# Arduino-4_Relays-Shield-V1.net
KiCad netlist of a schematic drawn in EAGLE
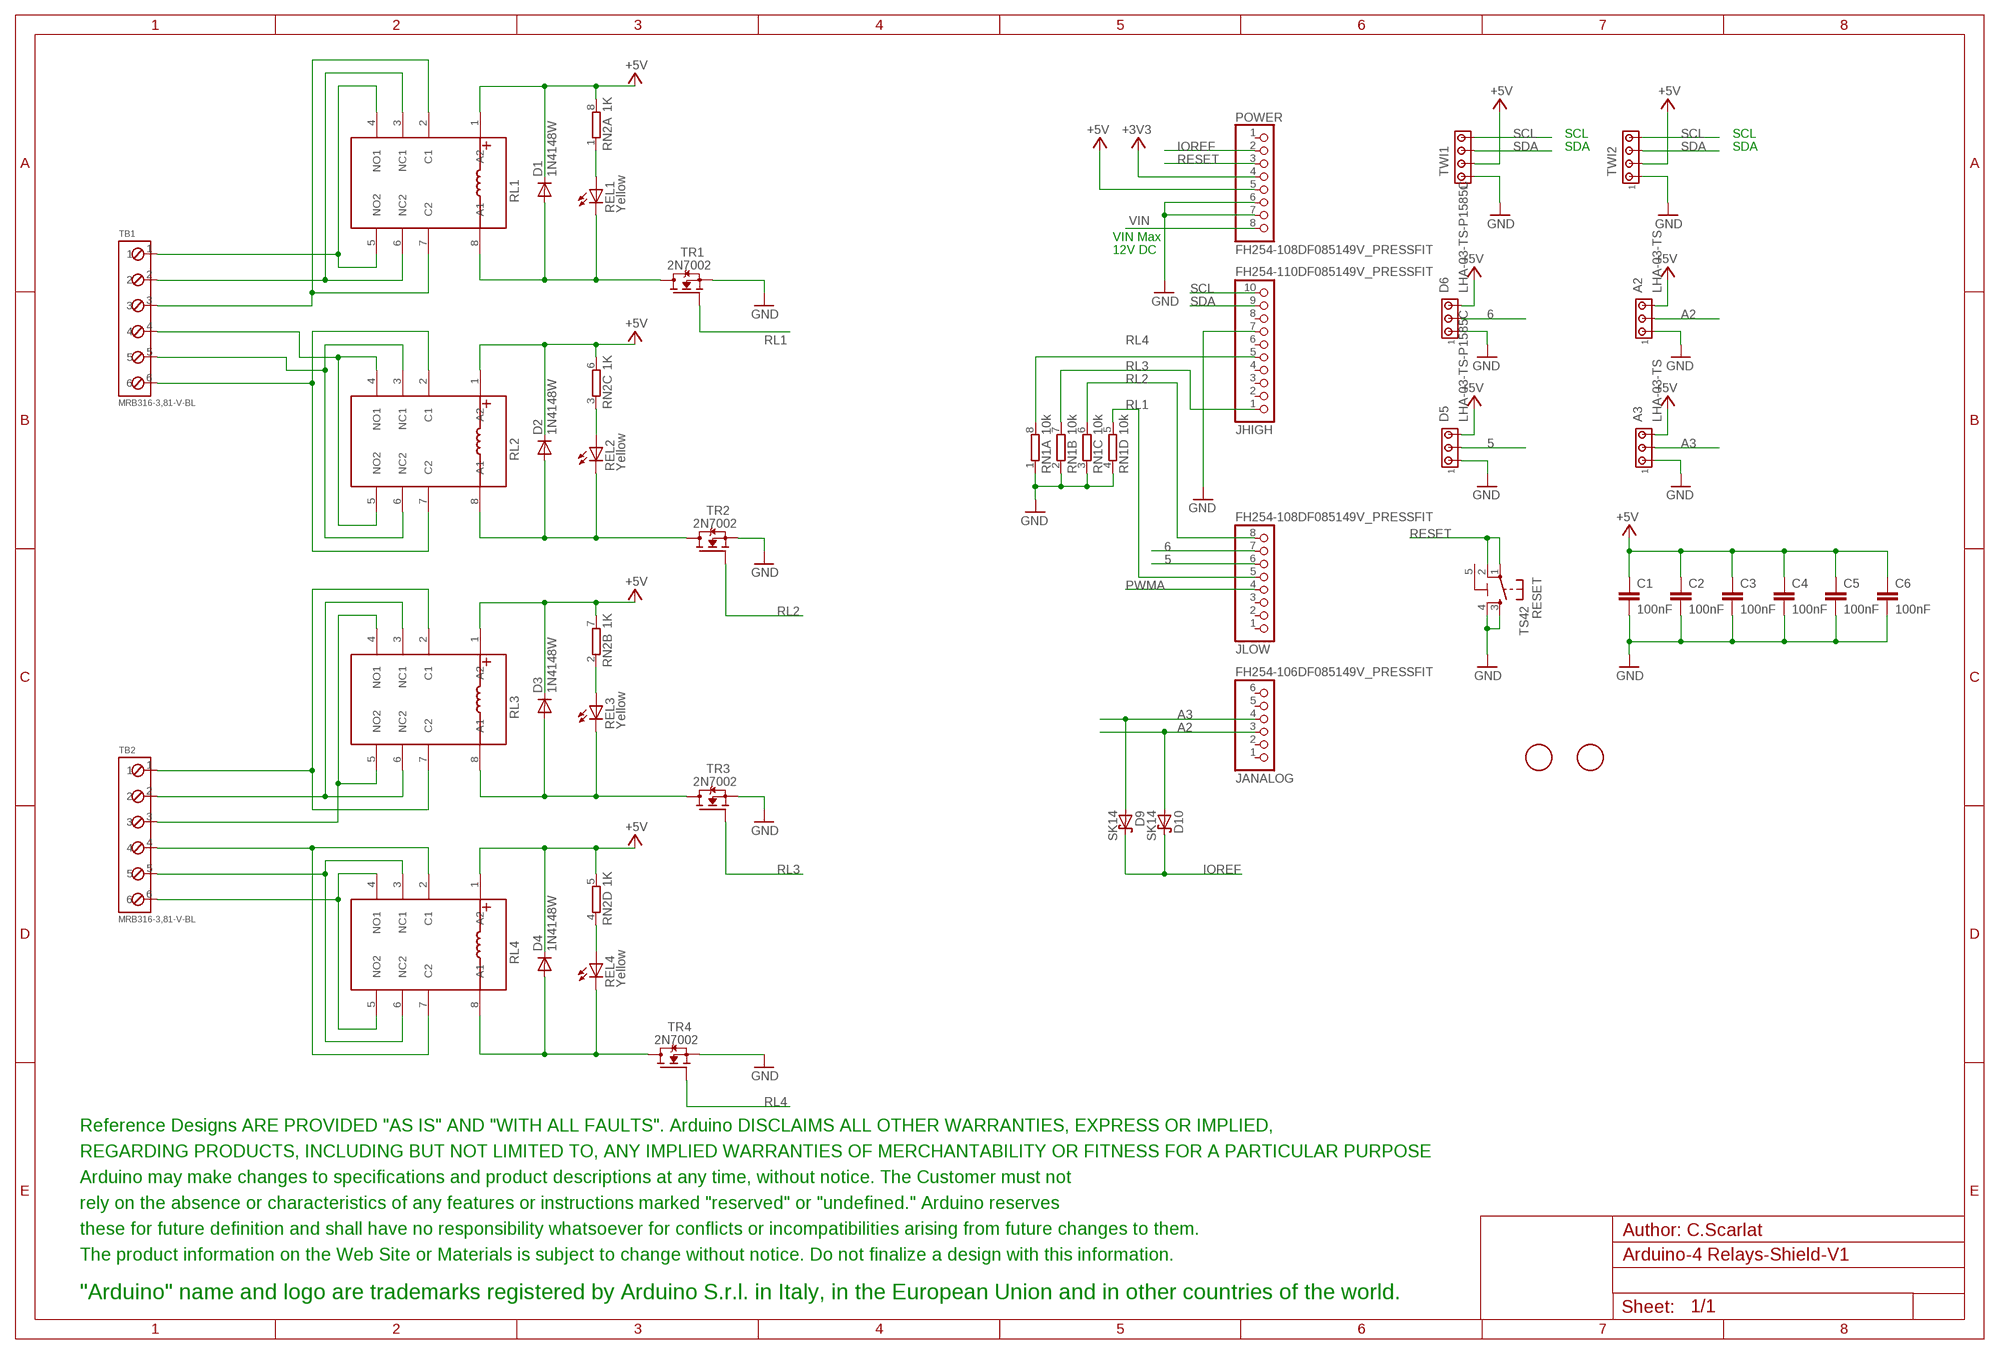
[diagram p0: schematic, sheet 1]

(export (version "E")
  (design (tool "Eeschema 10.0.6"))
  (components
    (comp (ref "A2")
      (value "LHA-03-TS")
      (footprint "eagle-import:10X03MTA")
      (libsource (lib "eagle-import") (part "0141_LHA-03-TS"))
    )
    (comp (ref "A3")
      (value "LHA-03-TS")
      (footprint "eagle-import:10X03MTA")
      (libsource (lib "eagle-import") (part "0141_LHA-03-TS"))
    )
    (comp (ref "C1")
      (value "100nF")
      (footprint "eagle-import:C0603-ROUND")
      (fields (field (name "PART_NUMBER") "cl10b104kbnc"))
      (libsource (lib "eagle-import") (part "0015_100NF_0603"))
    )
    (comp (ref "C2")
      (value "100nF")
      (footprint "eagle-import:C0603-ROUND")
      (fields (field (name "PART_NUMBER") "cl10b104kbnc"))
      (libsource (lib "eagle-import") (part "0015_100NF_0603"))
    )
    (comp (ref "C3")
      (value "100nF")
      (footprint "eagle-import:C0603-ROUND")
      (fields (field (name "PART_NUMBER") "cl10b104kbnc"))
      (libsource (lib "eagle-import") (part "0015_100NF_0603"))
    )
    (comp (ref "C4")
      (value "100nF")
      (footprint "eagle-import:C0603-ROUND")
      (fields (field (name "PART_NUMBER") "cl10b104kbnc"))
      (libsource (lib "eagle-import") (part "0015_100NF_0603"))
    )
    (comp (ref "C5")
      (value "100nF")
      (footprint "eagle-import:C0603-ROUND")
      (fields (field (name "PART_NUMBER") "cl10b104kbnc"))
      (libsource (lib "eagle-import") (part "0015_100NF_0603"))
    )
    (comp (ref "C6")
      (value "100nF")
      (footprint "eagle-import:C0603-ROUND")
      (fields (field (name "PART_NUMBER") "cl10b104kbnc"))
      (libsource (lib "eagle-import") (part "0015_100NF_0603"))
    )
    (comp (ref "D1")
      (value "1N4148W")
      (footprint "eagle-import:SOD123")
      (libsource (lib "eagle-import") (part "0290_1N4148W"))
    )
    (comp (ref "D2")
      (value "1N4148W")
      (footprint "eagle-import:SOD123")
      (libsource (lib "eagle-import") (part "0290_1N4148W"))
    )
    (comp (ref "D3")
      (value "1N4148W")
      (footprint "eagle-import:SOD123")
      (libsource (lib "eagle-import") (part "0290_1N4148W"))
    )
    (comp (ref "D4")
      (value "1N4148W")
      (footprint "eagle-import:SOD123")
      (libsource (lib "eagle-import") (part "0290_1N4148W"))
    )
    (comp (ref "D5")
      (value "LHA-03-TS-P1585C")
      (footprint "eagle-import:10X03MTA")
      (libsource (lib "eagle-import") (part "0481_LHA-03-TS-P1585C"))
    )
    (comp (ref "D6")
      (value "LHA-03-TS-P1585C")
      (footprint "eagle-import:10X03MTA")
      (libsource (lib "eagle-import") (part "0481_LHA-03-TS-P1585C"))
    )
    (comp (ref "D9")
      (value "SK14")
      (footprint "eagle-import:SMB")
      (libsource (lib "eagle-import") (part "0234_SK14"))
    )
    (comp (ref "D10")
      (value "SK14")
      (footprint "eagle-import:SMB")
      (libsource (lib "eagle-import") (part "0234_SK14"))
    )
    (comp (ref "FID2")
      (value "FIDUCIALMOUNT")
      (footprint "eagle-import:FIDUCIA-MOUNT")
      (libsource (lib "eagle-import") (part "FIDUCIALMOUNT"))
    )
    (comp (ref "FID3")
      (value "FIDUCIALMOUNT")
      (footprint "eagle-import:FIDUCIA-MOUNT")
      (libsource (lib "eagle-import") (part "FIDUCIALMOUNT"))
    )
    (comp (ref "JANALOG")
      (value "FH254-106DF085149V_PRESSFIT")
      (footprint "eagle-import:1X06-TH-PRESSFIT")
      (fields (field (name "PART_NUMBER") "FH254-106DF085149V"))
      (libsource (lib "eagle-import") (part "0061_FH254-106DF085149VPRESSFIT"))
    )
    (comp (ref "JHIGH")
      (value "FH254-110DF085149V_PRESSFIT")
      (footprint "eagle-import:1X10-TH-PRESSFIT")
      (fields (field (name "PART_NUMBER") "FH254-110DF085149V"))
      (libsource (lib "eagle-import") (part "0063_FH254-110DF085149VPRESSFIT"))
    )
    (comp (ref "JLOW")
      (value "FH254-108DF085149V_PRESSFIT")
      (footprint "eagle-import:1X08-TH-PRESSFIT")
      (fields (field (name "PART_NUMBER") "FH254-108DF085149V"))
      (libsource (lib "eagle-import") (part "0062_FH254-108DF085149VPRESSFIT"))
    )
    (comp (ref "POWER")
      (value "FH254-108DF085149V_PRESSFIT")
      (footprint "eagle-import:1X08-TH-PRESSFIT")
      (fields (field (name "PART_NUMBER") "FH254-108DF085149V"))
      (libsource (lib "eagle-import") (part "0062_FH254-108DF085149VPRESSFIT"))
    )
    (comp (ref "REL1")
      (value "Yellow")
      (footprint "eagle-import:CHIPLED_0805")
      (fields (field (name "PART_NUMBER") "KPT-2012YC"))
      (libsource (lib "eagle-import") (part "0044_KPT-2012YC"))
    )
    (comp (ref "REL2")
      (value "Yellow")
      (footprint "eagle-import:CHIPLED_0805")
      (fields (field (name "PART_NUMBER") "KPT-2012YC"))
      (libsource (lib "eagle-import") (part "0044_KPT-2012YC"))
    )
    (comp (ref "REL3")
      (value "Yellow")
      (footprint "eagle-import:CHIPLED_0805")
      (fields (field (name "PART_NUMBER") "KPT-2012YC"))
      (libsource (lib "eagle-import") (part "0044_KPT-2012YC"))
    )
    (comp (ref "REL4")
      (value "Yellow")
      (footprint "eagle-import:CHIPLED_0805")
      (fields (field (name "PART_NUMBER") "KPT-2012YC"))
      (libsource (lib "eagle-import") (part "0044_KPT-2012YC"))
    )
    (comp (ref "RESET")
      (value "TS42")
      (footprint "eagle-import:TS42")
      (fields (field (name "PART_NUMBER") "IT-1157AHNP-160G-G_GTR"))
      (libsource (lib "eagle-import") (part "0946_TS42031-160W-TR-7260"))
    )
    (comp (ref "RL1")
      (value "1045_G5V-2-H1")
      (footprint "eagle-import:RELE'-30SSERIES-DIL-2X")
      (fields (field (name "PART_NUMBER") "G5V-2-H1"))
      (libsource (lib "eagle-import") (part "1045_G5V-2-H1"))
    )
    (comp (ref "RL2")
      (value "1045_G5V-2-H1")
      (footprint "eagle-import:RELE'-30SSERIES-DIL-2X")
      (fields (field (name "PART_NUMBER") "G5V-2-H1"))
      (libsource (lib "eagle-import") (part "1045_G5V-2-H1"))
    )
    (comp (ref "RL3")
      (value "1045_G5V-2-H1")
      (footprint "eagle-import:RELE'-30SSERIES-DIL-2X")
      (fields (field (name "PART_NUMBER") "G5V-2-H1"))
      (libsource (lib "eagle-import") (part "1045_G5V-2-H1"))
    )
    (comp (ref "RL4")
      (value "1045_G5V-2-H1")
      (footprint "eagle-import:RELE'-30SSERIES-DIL-2X")
      (fields (field (name "PART_NUMBER") "G5V-2-H1"))
      (libsource (lib "eagle-import") (part "1045_G5V-2-H1"))
    )
    (comp (ref "RN1")
      (value "10k")
      (footprint "eagle-import:CAY16")
      (fields (field (name "PART_NUMBER") "064R_10K_/_CAY16-103J4LF"))
      (libsource (lib "eagle-import") (part "0016_064R_10K_/_CAY16-103J4LF"))
    )
    (comp (ref "RN2")
      (value "1K")
      (footprint "eagle-import:CAY16")
      (fields (field (name "PART_NUMBER") "064R_1K_/_CAY16-102J4LF"))
      (libsource (lib "eagle-import") (part "0005_064R_1K_/_CAY16-102J4LF"))
    )
    (comp (ref "TB1")
      (value "MRB316-3,81-V-BL")
      (footprint "eagle-import:MRB316-3,81-V-BL")
      (libsource (lib "eagle-import") (part "0698_MRB316-3,81-V-BL"))
    )
    (comp (ref "TB2")
      (value "MRB316-3,81-V-BL")
      (footprint "eagle-import:MRB316-3,81-V-BL")
      (libsource (lib "eagle-import") (part "0698_MRB316-3,81-V-BL"))
    )
    (comp (ref "TR1")
      (value "2N7002")
      (footprint "eagle-import:SOT-23")
      (libsource (lib "eagle-import") (part "1612_2N7002LT1G"))
    )
    (comp (ref "TR2")
      (value "2N7002")
      (footprint "eagle-import:SOT-23")
      (libsource (lib "eagle-import") (part "1612_2N7002LT1G"))
    )
    (comp (ref "TR3")
      (value "2N7002")
      (footprint "eagle-import:SOT-23")
      (libsource (lib "eagle-import") (part "1612_2N7002LT1G"))
    )
    (comp (ref "TR4")
      (value "2N7002")
      (footprint "eagle-import:SOT-23")
      (libsource (lib "eagle-import") (part "1612_2N7002LT1G"))
    )
    (comp (ref "TWI1")
      (value "0205_LHA-04-TS__4X1_VERTICALE_BIANCO_P_2,54")
      (footprint "eagle-import:10X04MTA")
      (fields (field (name "PART_NUMBER") "LHA-04-TS__4x1_Verticale_Bianco_p_2,54"))
      (libsource (lib "eagle-import") (part "0205_LHA-04-TS__4X1_VERTICALE_BIANCO_P_2,54"))
    )
    (comp (ref "TWI2")
      (value "0205_LHA-04-TS__4X1_VERTICALE_BIANCO_P_2,54")
      (footprint "eagle-import:10X04MTA")
      (fields (field (name "PART_NUMBER") "LHA-04-TS__4x1_Verticale_Bianco_p_2,54"))
      (libsource (lib "eagle-import") (part "0205_LHA-04-TS__4X1_VERTICALE_BIANCO_P_2,54"))
    )
    (comp (ref "U$2")
      (value "DISCLAIMER-SMALL")
      (footprint "eagle-import:DISCLAIMER")
      (libsource (lib "eagle-import") (part "DISCLAIMER-SMALL"))
    )
  )
  (nets
    (net (code "1") (name "+3V3") (class "Default")
      (node (ref "POWER") (pin "4") (pinfunction "4_4") (pintype "passive"))
    )
    (net (code "2") (name "+5V") (class "Default")
      (node (ref "A2") (pin "3") (pinfunction "3_3") (pintype "passive"))
      (node (ref "A3") (pin "3") (pinfunction "3_3") (pintype "passive"))
      (node (ref "C1") (pin "1") (pinfunction "1_1") (pintype "passive"))
      (node (ref "C2") (pin "1") (pinfunction "1_1") (pintype "passive"))
      (node (ref "C3") (pin "1") (pinfunction "1_1") (pintype "passive"))
      (node (ref "C4") (pin "1") (pinfunction "1_1") (pintype "passive"))
      (node (ref "C5") (pin "1") (pinfunction "1_1") (pintype "passive"))
      (node (ref "C6") (pin "1") (pinfunction "1_1") (pintype "passive"))
      (node (ref "D1") (pin "C") (pinfunction "C_C") (pintype "passive"))
      (node (ref "D2") (pin "C") (pinfunction "C_C") (pintype "passive"))
      (node (ref "D3") (pin "C") (pinfunction "C_C") (pintype "passive"))
      (node (ref "D4") (pin "C") (pinfunction "C_C") (pintype "passive"))
      (node (ref "D5") (pin "3") (pinfunction "3_3") (pintype "passive"))
      (node (ref "D6") (pin "3") (pinfunction "3_3") (pintype "passive"))
      (node (ref "POWER") (pin "5") (pinfunction "5_5") (pintype "passive"))
      (node (ref "RL1") (pin "1") (pinfunction "A2_1") (pintype "bidirectional"))
      (node (ref "RL2") (pin "1") (pinfunction "A2_1") (pintype "bidirectional"))
      (node (ref "RL3") (pin "1") (pinfunction "A2_1") (pintype "bidirectional"))
      (node (ref "RL4") (pin "1") (pinfunction "A2_1") (pintype "bidirectional"))
      (node (ref "RN2") (pin "5") (pinfunction "2_5") (pintype "passive"))
      (node (ref "RN2") (pin "6") (pinfunction "2_6") (pintype "passive"))
      (node (ref "RN2") (pin "7") (pinfunction "2_7") (pintype "passive"))
      (node (ref "RN2") (pin "8") (pinfunction "2_8") (pintype "passive"))
      (node (ref "TWI1") (pin "2") (pinfunction "2_2") (pintype "passive"))
      (node (ref "TWI2") (pin "2") (pinfunction "2_2") (pintype "passive"))
    )
    (net (code "3") (name "/5") (class "Default")
      (node (ref "D5") (pin "2") (pinfunction "2_2") (pintype "passive"))
      (node (ref "JLOW") (pin "6") (pinfunction "6_6") (pintype "passive"))
    )
    (net (code "4") (name "/5-GND") (class "Default")
      (node (ref "RESET") (pin "5") (pinfunction "5-GND_5") (pintype "power_in"))
    )
    (net (code "5") (name "/6") (class "Default")
      (node (ref "D6") (pin "2") (pinfunction "2_2") (pintype "passive"))
      (node (ref "JLOW") (pin "7") (pinfunction "7_7") (pintype "passive"))
    )
    (net (code "6") (name "/A2") (class "Default")
      (node (ref "A2") (pin "2") (pinfunction "2_2") (pintype "passive"))
      (node (ref "D10") (pin "A") (pinfunction "A_A") (pintype "passive"))
      (node (ref "JANALOG") (pin "3") (pinfunction "3_3") (pintype "passive"))
    )
    (net (code "7") (name "/A3") (class "Default")
      (node (ref "A3") (pin "2") (pinfunction "2_2") (pintype "passive"))
      (node (ref "D9") (pin "A") (pinfunction "A_A") (pintype "passive"))
      (node (ref "JANALOG") (pin "4") (pinfunction "4_4") (pintype "passive"))
    )
    (net (code "8") (name "/IOREF") (class "Default")
      (node (ref "D10") (pin "C") (pinfunction "C_C") (pintype "passive"))
      (node (ref "D9") (pin "C") (pinfunction "C_C") (pintype "passive"))
      (node (ref "POWER") (pin "2") (pinfunction "2_2") (pintype "passive"))
    )
    (net (code "9") (name "/PWMA") (class "Default")
      (node (ref "JLOW") (pin "4") (pinfunction "4_4") (pintype "passive"))
    )
    (net (code "10") (name "/RESET") (class "Default")
      (node (ref "POWER") (pin "3") (pinfunction "3_3") (pintype "passive"))
      (node (ref "RESET") (pin "1") (pinfunction "1_1") (pintype "passive"))
      (node (ref "RESET") (pin "2") (pinfunction "2_2") (pintype "passive"))
    )
    (net (code "11") (name "/RL1") (class "Default")
      (node (ref "JLOW") (pin "5") (pinfunction "5_5") (pintype "passive"))
      (node (ref "RN1") (pin "5") (pinfunction "2_5") (pintype "passive"))
      (node (ref "TR1") (pin "3") (pinfunction "G_3") (pintype "passive"))
    )
    (net (code "12") (name "/RL2") (class "Default")
      (node (ref "JLOW") (pin "8") (pinfunction "8_8") (pintype "passive"))
      (node (ref "RN1") (pin "6") (pinfunction "2_6") (pintype "passive"))
      (node (ref "TR2") (pin "3") (pinfunction "G_3") (pintype "passive"))
    )
    (net (code "13") (name "/RL3") (class "Default")
      (node (ref "JHIGH") (pin "1") (pinfunction "1_1") (pintype "passive"))
      (node (ref "RN1") (pin "7") (pinfunction "2_7") (pintype "passive"))
      (node (ref "TR3") (pin "3") (pinfunction "G_3") (pintype "passive"))
    )
    (net (code "14") (name "/RL4") (class "Default")
      (node (ref "JHIGH") (pin "5") (pinfunction "5_5") (pintype "passive"))
      (node (ref "RN1") (pin "8") (pinfunction "2_8") (pintype "passive"))
      (node (ref "TR4") (pin "3") (pinfunction "G_3") (pintype "passive"))
    )
    (net (code "15") (name "/SCL") (class "Default")
      (node (ref "JHIGH") (pin "10") (pinfunction "10_10") (pintype "passive"))
      (node (ref "TWI1") (pin "4") (pinfunction "4_4") (pintype "passive"))
      (node (ref "TWI2") (pin "4") (pinfunction "4_4") (pintype "passive"))
    )
    (net (code "16") (name "/SDA") (class "Default")
      (node (ref "JHIGH") (pin "9") (pinfunction "9_9") (pintype "passive"))
      (node (ref "TWI1") (pin "3") (pinfunction "3_3") (pintype "passive"))
      (node (ref "TWI2") (pin "3") (pinfunction "3_3") (pintype "passive"))
    )
    (net (code "17") (name "/VIN") (class "Default")
      (node (ref "POWER") (pin "8") (pinfunction "8_8") (pintype "passive"))
    )
    (net (code "18") (name "GND") (class "Default")
      (node (ref "A2") (pin "1") (pinfunction "1_1") (pintype "passive"))
      (node (ref "A3") (pin "1") (pinfunction "1_1") (pintype "passive"))
      (node (ref "C1") (pin "2") (pinfunction "2_2") (pintype "passive"))
      (node (ref "C2") (pin "2") (pinfunction "2_2") (pintype "passive"))
      (node (ref "C3") (pin "2") (pinfunction "2_2") (pintype "passive"))
      (node (ref "C4") (pin "2") (pinfunction "2_2") (pintype "passive"))
      (node (ref "C5") (pin "2") (pinfunction "2_2") (pintype "passive"))
      (node (ref "C6") (pin "2") (pinfunction "2_2") (pintype "passive"))
      (node (ref "D5") (pin "1") (pinfunction "1_1") (pintype "passive"))
      (node (ref "D6") (pin "1") (pinfunction "1_1") (pintype "passive"))
      (node (ref "JHIGH") (pin "7") (pinfunction "7_7") (pintype "passive"))
      (node (ref "POWER") (pin "6") (pinfunction "6_6") (pintype "passive"))
      (node (ref "POWER") (pin "7") (pinfunction "7_7") (pintype "passive"))
      (node (ref "RESET") (pin "3") (pinfunction "3_3") (pintype "passive"))
      (node (ref "RESET") (pin "4") (pinfunction "4_4") (pintype "passive"))
      (node (ref "RN1") (pin "1") (pinfunction "1_1") (pintype "passive"))
      (node (ref "RN1") (pin "2") (pinfunction "1_2") (pintype "passive"))
      (node (ref "RN1") (pin "3") (pinfunction "1_3") (pintype "passive"))
      (node (ref "RN1") (pin "4") (pinfunction "1_4") (pintype "passive"))
      (node (ref "TR1") (pin "2") (pinfunction "S_2") (pintype "passive"))
      (node (ref "TR2") (pin "2") (pinfunction "S_2") (pintype "passive"))
      (node (ref "TR3") (pin "2") (pinfunction "S_2") (pintype "passive"))
      (node (ref "TR4") (pin "2") (pinfunction "S_2") (pintype "passive"))
      (node (ref "TWI1") (pin "1") (pinfunction "1_1") (pintype "passive"))
      (node (ref "TWI2") (pin "1") (pinfunction "1_1") (pintype "passive"))
    )
    (net (code "19") (name "Net-(REL1-PadA)") (class "Default")
      (node (ref "REL1") (pin "A") (pinfunction "A_A") (pintype "passive"))
      (node (ref "RN2") (pin "1") (pinfunction "1_1") (pintype "passive"))
    )
    (net (code "20") (name "Net-(RL1-A1)") (class "Default")
      (node (ref "D1") (pin "A") (pinfunction "A_A") (pintype "passive"))
      (node (ref "REL1") (pin "C") (pinfunction "C_C") (pintype "passive"))
      (node (ref "RL1") (pin "8") (pinfunction "A1_8") (pintype "bidirectional"))
      (node (ref "TR1") (pin "1") (pinfunction "D_1") (pintype "passive"))
    )
    (net (code "21") (name "Net-(RL1-C1)") (class "Default")
      (node (ref "RL1") (pin "2") (pinfunction "C1_2") (pintype "bidirectional"))
      (node (ref "RL1") (pin "7") (pinfunction "C2_7") (pintype "bidirectional"))
      (node (ref "TB1") (pin "3") (pinfunction "3_3") (pintype "bidirectional"))
    )
    (net (code "22") (name "Net-(RL1-NC1)") (class "Default")
      (node (ref "RL1") (pin "3") (pinfunction "NC1_3") (pintype "bidirectional"))
      (node (ref "RL1") (pin "6") (pinfunction "NC2_6") (pintype "bidirectional"))
      (node (ref "TB1") (pin "2") (pinfunction "2_2") (pintype "bidirectional"))
    )
    (net (code "23") (name "Net-(RL1-NO1)") (class "Default")
      (node (ref "RL1") (pin "4") (pinfunction "NO1_4") (pintype "bidirectional"))
      (node (ref "RL1") (pin "5") (pinfunction "NO2_5") (pintype "bidirectional"))
      (node (ref "TB1") (pin "1") (pinfunction "1_1") (pintype "bidirectional"))
    )
    (net (code "24") (name "Net-(RL2-A1)") (class "Default")
      (node (ref "D2") (pin "A") (pinfunction "A_A") (pintype "passive"))
      (node (ref "REL2") (pin "C") (pinfunction "C_C") (pintype "passive"))
      (node (ref "RL2") (pin "8") (pinfunction "A1_8") (pintype "bidirectional"))
      (node (ref "TR2") (pin "1") (pinfunction "D_1") (pintype "passive"))
    )
    (net (code "25") (name "Net-(RL2-C1)") (class "Default")
      (node (ref "RL2") (pin "2") (pinfunction "C1_2") (pintype "bidirectional"))
      (node (ref "RL2") (pin "7") (pinfunction "C2_7") (pintype "bidirectional"))
      (node (ref "TB1") (pin "6") (pinfunction "6_6") (pintype "bidirectional"))
    )
    (net (code "26") (name "Net-(RL2-NC1)") (class "Default")
      (node (ref "RL2") (pin "3") (pinfunction "NC1_3") (pintype "bidirectional"))
      (node (ref "RL2") (pin "6") (pinfunction "NC2_6") (pintype "bidirectional"))
      (node (ref "TB1") (pin "5") (pinfunction "5_5") (pintype "bidirectional"))
    )
    (net (code "27") (name "Net-(RL2-NO1)") (class "Default")
      (node (ref "RL2") (pin "4") (pinfunction "NO1_4") (pintype "bidirectional"))
      (node (ref "RL2") (pin "5") (pinfunction "NO2_5") (pintype "bidirectional"))
      (node (ref "TB1") (pin "4") (pinfunction "4_4") (pintype "bidirectional"))
    )
    (net (code "28") (name "Net-(RL3-A1)") (class "Default")
      (node (ref "D3") (pin "A") (pinfunction "A_A") (pintype "passive"))
      (node (ref "REL3") (pin "C") (pinfunction "C_C") (pintype "passive"))
      (node (ref "RL3") (pin "8") (pinfunction "A1_8") (pintype "bidirectional"))
      (node (ref "TR3") (pin "1") (pinfunction "D_1") (pintype "passive"))
    )
    (net (code "29") (name "Net-(RL3-C1)") (class "Default")
      (node (ref "RL3") (pin "2") (pinfunction "C1_2") (pintype "bidirectional"))
      (node (ref "RL3") (pin "7") (pinfunction "C2_7") (pintype "bidirectional"))
      (node (ref "TB2") (pin "1") (pinfunction "1_1") (pintype "bidirectional"))
    )
    (net (code "30") (name "Net-(RL3-NC1)") (class "Default")
      (node (ref "RL3") (pin "3") (pinfunction "NC1_3") (pintype "bidirectional"))
      (node (ref "RL3") (pin "6") (pinfunction "NC2_6") (pintype "bidirectional"))
      (node (ref "TB2") (pin "2") (pinfunction "2_2") (pintype "bidirectional"))
    )
    (net (code "31") (name "Net-(RL3-NO1)") (class "Default")
      (node (ref "RL3") (pin "4") (pinfunction "NO1_4") (pintype "bidirectional"))
      (node (ref "RL3") (pin "5") (pinfunction "NO2_5") (pintype "bidirectional"))
      (node (ref "TB2") (pin "3") (pinfunction "3_3") (pintype "bidirectional"))
    )
    (net (code "32") (name "Net-(RL4-A1)") (class "Default")
      (node (ref "D4") (pin "A") (pinfunction "A_A") (pintype "passive"))
      (node (ref "REL4") (pin "C") (pinfunction "C_C") (pintype "passive"))
      (node (ref "RL4") (pin "8") (pinfunction "A1_8") (pintype "bidirectional"))
      (node (ref "TR4") (pin "1") (pinfunction "D_1") (pintype "passive"))
    )
    (net (code "33") (name "Net-(RL4-C1)") (class "Default")
      (node (ref "RL4") (pin "2") (pinfunction "C1_2") (pintype "bidirectional"))
      (node (ref "RL4") (pin "7") (pinfunction "C2_7") (pintype "bidirectional"))
      (node (ref "TB2") (pin "4") (pinfunction "4_4") (pintype "bidirectional"))
    )
    (net (code "34") (name "Net-(RL4-NC1)") (class "Default")
      (node (ref "RL4") (pin "3") (pinfunction "NC1_3") (pintype "bidirectional"))
      (node (ref "RL4") (pin "6") (pinfunction "NC2_6") (pintype "bidirectional"))
      (node (ref "TB2") (pin "5") (pinfunction "5_5") (pintype "bidirectional"))
    )
    (net (code "35") (name "Net-(RL4-NO1)") (class "Default")
      (node (ref "RL4") (pin "4") (pinfunction "NO1_4") (pintype "bidirectional"))
      (node (ref "RL4") (pin "5") (pinfunction "NO2_5") (pintype "bidirectional"))
      (node (ref "TB2") (pin "6") (pinfunction "6_6") (pintype "bidirectional"))
    )
    (net (code "36") (name "Net-(RN2B-1)") (class "Default")
      (node (ref "REL3") (pin "A") (pinfunction "A_A") (pintype "passive"))
      (node (ref "RN2") (pin "2") (pinfunction "1_2") (pintype "passive"))
    )
    (net (code "37") (name "Net-(RN2C-1)") (class "Default")
      (node (ref "REL2") (pin "A") (pinfunction "A_A") (pintype "passive"))
      (node (ref "RN2") (pin "3") (pinfunction "1_3") (pintype "passive"))
    )
    (net (code "38") (name "Net-(RN2D-1)") (class "Default")
      (node (ref "REL4") (pin "A") (pinfunction "A_A") (pintype "passive"))
      (node (ref "RN2") (pin "4") (pinfunction "1_4") (pintype "passive"))
    )
    (net (code "39") (name "unconnected-(JANALOG-Pad1)") (class "Default")
      (node (ref "JANALOG") (pin "1") (pinfunction "1_1") (pintype "passive"))
    )
    (net (code "40") (name "unconnected-(JANALOG-Pad2)") (class "Default")
      (node (ref "JANALOG") (pin "2") (pinfunction "2_2") (pintype "passive"))
    )
    (net (code "41") (name "unconnected-(JANALOG-Pad5)") (class "Default")
      (node (ref "JANALOG") (pin "5") (pinfunction "5_5") (pintype "passive"))
    )
    (net (code "42") (name "unconnected-(JANALOG-Pad6)") (class "Default")
      (node (ref "JANALOG") (pin "6") (pinfunction "6_6") (pintype "passive"))
    )
    (net (code "43") (name "unconnected-(JHIGH-Pad2)") (class "Default")
      (node (ref "JHIGH") (pin "2") (pinfunction "2_2") (pintype "passive"))
    )
    (net (code "44") (name "unconnected-(JHIGH-Pad3)") (class "Default")
      (node (ref "JHIGH") (pin "3") (pinfunction "3_3") (pintype "passive"))
    )
    (net (code "45") (name "unconnected-(JHIGH-Pad4)") (class "Default")
      (node (ref "JHIGH") (pin "4") (pinfunction "4_4") (pintype "passive"))
    )
    (net (code "46") (name "unconnected-(JHIGH-Pad6)") (class "Default")
      (node (ref "JHIGH") (pin "6") (pinfunction "6_6") (pintype "passive"))
    )
    (net (code "47") (name "unconnected-(JHIGH-Pad8)") (class "Default")
      (node (ref "JHIGH") (pin "8") (pinfunction "8_8") (pintype "passive"))
    )
    (net (code "48") (name "unconnected-(JLOW-Pad1)") (class "Default")
      (node (ref "JLOW") (pin "1") (pinfunction "1_1") (pintype "passive"))
    )
    (net (code "49") (name "unconnected-(JLOW-Pad2)") (class "Default")
      (node (ref "JLOW") (pin "2") (pinfunction "2_2") (pintype "passive"))
    )
    (net (code "50") (name "unconnected-(JLOW-Pad3)") (class "Default")
      (node (ref "JLOW") (pin "3") (pinfunction "3_3") (pintype "passive"))
    )
    (net (code "51") (name "unconnected-(POWER-Pad1)") (class "Default")
      (node (ref "POWER") (pin "1") (pinfunction "1_1") (pintype "passive"))
    )
  )
)
